# SCH_System.net
KiCad netlist of a schematic drawn in Altium Designer
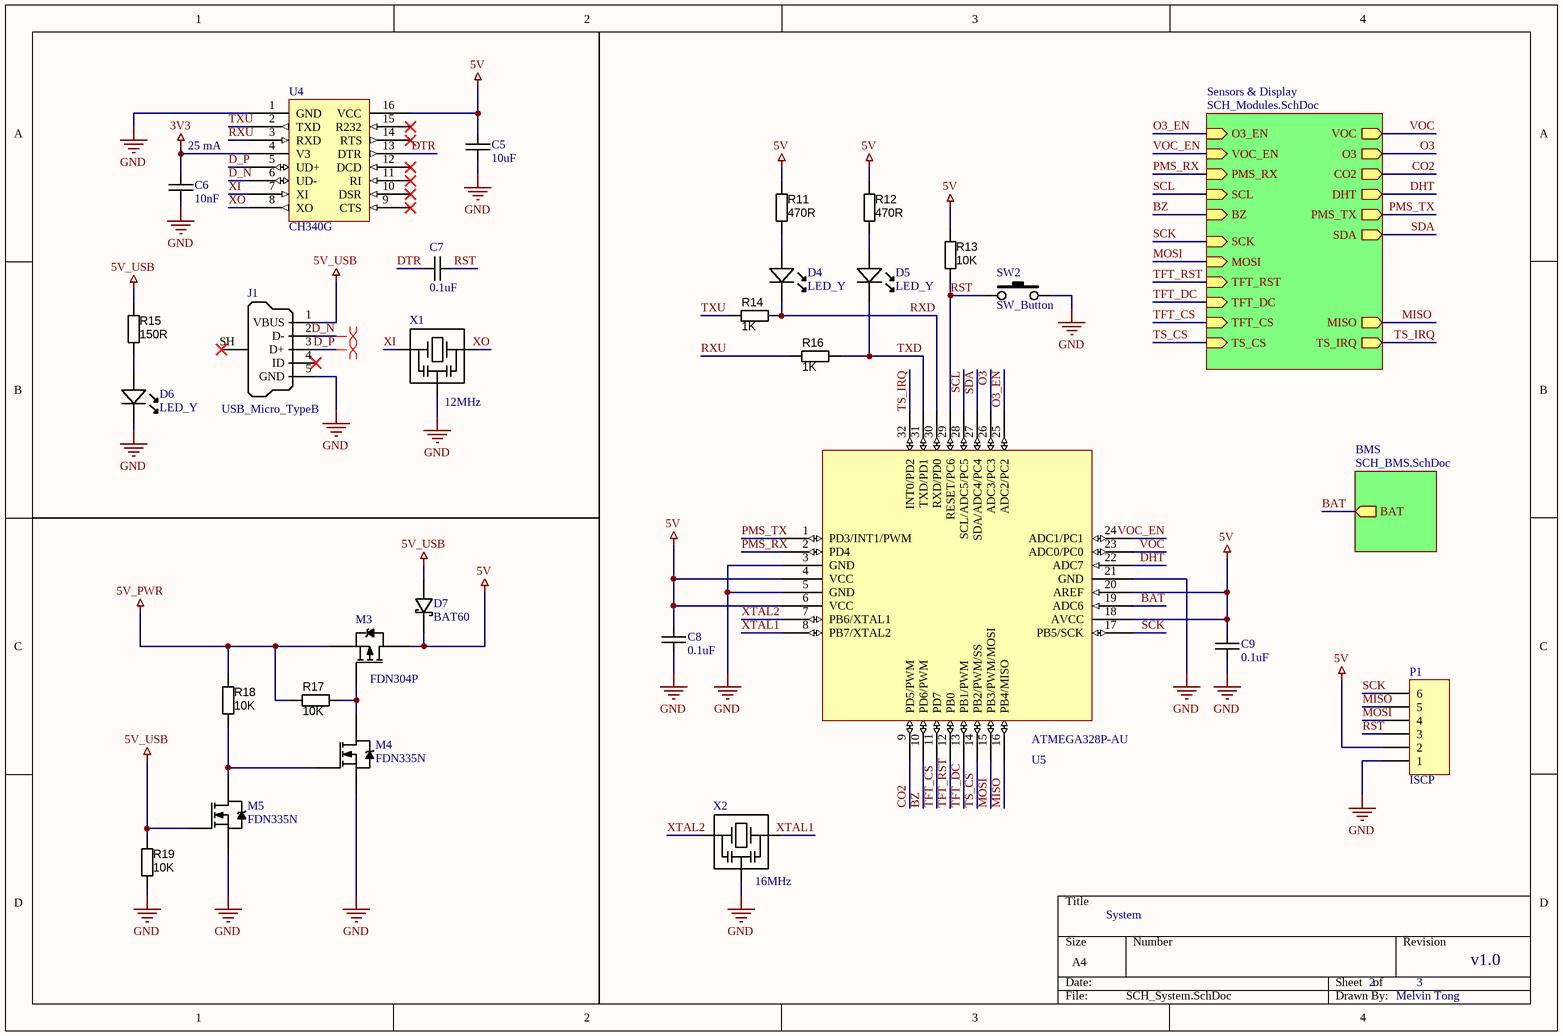
[diagram p0: SCH_System.SchDoc]

(export (version "E")
  (design (tool "Eeschema 10.0.6"))
  (components
    (comp (ref "C5")
      (value "10uF")
      (footprint "CAP_0805")
      (description "SMD 0805")
      (libsource (lib "SchLib_AirMeter") (part "CAP_10uF"))
    )
    (comp (ref "C6")
      (value "10nF")
      (footprint "CAP_0805")
      (description "SMD 0805")
      (libsource (lib "SchLib_AirMeter") (part "CAP_10nF"))
    )
    (comp (ref "C7")
      (value "0.1uF")
      (footprint "CAP_0805")
      (description "SMD 0805")
      (libsource (lib "SchLib_AirMeter") (part "CAP_0.1uF"))
    )
    (comp (ref "C8")
      (value "0.1uF")
      (footprint "CAP_0805")
      (description "SMD 0805")
      (libsource (lib "SchLib_AirMeter") (part "CAP_0.1uF"))
    )
    (comp (ref "C9")
      (value "0.1uF")
      (footprint "CAP_0805")
      (description "SMD 0805")
      (libsource (lib "SchLib_AirMeter") (part "CAP_0.1uF"))
    )
    (comp (ref "D4")
      (value "LED_Y")
      (footprint "LED_0805")
      (description "SMD_0805 2.4V")
      (libsource (lib "SchLib_AirMeter") (part "LED_Y"))
    )
    (comp (ref "D5")
      (value "LED_Y")
      (footprint "LED_0805")
      (description "SMD_0805 2.4V")
      (libsource (lib "SchLib_AirMeter") (part "LED_Y"))
    )
    (comp (ref "D6")
      (value "LED_Y")
      (footprint "LED_0805")
      (description "SMD_0805 2.4V")
      (libsource (lib "SchLib_AirMeter") (part "LED_Y"))
    )
    (comp (ref "D7")
      (value "BAT60")
      (footprint "SOD323")
      (description "Schottky Diode 3A, Vf~0.24V, Vr=10V")
      (libsource (lib "SchLib_AirMeter") (part "BAT60"))
    )
    (comp (ref "J1")
      (value "USB_Micro_TypeB")
      (footprint "USB_Micro_TypeB")
      (libsource (lib "SchLib_AirMeter") (part "USB_Micro_TypeB"))
    )
    (comp (ref "M3")
      (value "FDN304P")
      (footprint "SOT23_213")
      (libsource (lib "SchLib_AirMeter") (part "PMOS"))
    )
    (comp (ref "M4")
      (value "FDN335N")
      (footprint "SOT23_213")
      (libsource (lib "SchLib_AirMeter") (part "NMOS"))
    )
    (comp (ref "M5")
      (value "FDN335N")
      (footprint "SOT23_213")
      (libsource (lib "SchLib_AirMeter") (part "NMOS"))
    )
    (comp (ref "P1")
      (value "ISCP")
      (footprint "HDR1X6")
      (description "Header, 6-Pin")
      (fields (field (name "PUBLISHER") "Altium Limited"))
      (libsource (lib "Miscellaneous Connectors") (part "Header 6"))
    )
    (comp (ref "R11")
      (value "470R")
      (footprint "RESC3216X70N")
      (description "Resistor SMD, 1206")
      (libsource (lib "Schlib_Sword") (part "RES_470R"))
    )
    (comp (ref "R12")
      (value "470R")
      (footprint "RESC3216X70N")
      (description "Resistor SMD, 1206")
      (libsource (lib "") (part "RES_470R_1"))
    )
    (comp (ref "R13")
      (value "10K")
      (footprint "RESC3216X70N")
      (description "Resistor SMD, 1206")
      (libsource (lib "SchLib_AirMeter") (part "RES_10K"))
    )
    (comp (ref "R14")
      (value "1K")
      (footprint "RESC3216X70N")
      (description "Resistor SMD, 1206")
      (libsource (lib "SchLib_AirMeter") (part "RES_1K"))
    )
    (comp (ref "R15")
      (value "150R")
      (footprint "RESC3216X70N")
      (description "Resistor SMD, 1206")
      (libsource (lib "SchLib_AirMeter") (part "RES_150R"))
    )
    (comp (ref "R16")
      (value "1K")
      (footprint "RESC3216X70N")
      (description "Resistor SMD, 1206")
      (libsource (lib "SchLib_AirMeter") (part "RES_1K"))
    )
    (comp (ref "R17")
      (value "10K")
      (footprint "RESC3216X70N")
      (description "Resistor SMD, 1206")
      (libsource (lib "") (part "RES_10K_1"))
    )
    (comp (ref "R18")
      (value "10K")
      (footprint "RESC3216X70N")
      (description "Resistor SMD, 1206")
      (libsource (lib "SchLib_AirMeter") (part "RES_10K"))
    )
    (comp (ref "R19")
      (value "10K")
      (footprint "RESC3216X70N")
      (description "Resistor SMD, 1206")
      (libsource (lib "SchLib_AirMeter") (part "RES_10K"))
    )
    (comp (ref "SW2")
      (value "SW_Button")
      (footprint "Button_4x4x1.5")
      (libsource (lib "SchLib_AirMeter") (part "SW_Button"))
    )
    (comp (ref "U4")
      (value "CH340G")
      (footprint "CH340G")
      (libsource (lib "SchLib_AirMeter") (part "CH340G"))
    )
    (comp (ref "U5")
      (value "ATMEGA328P-AU")
      (footprint "ATMEGA328P-AU")
      (libsource (lib "SchLib_AirMeter") (part "ATMEGA328P-AU"))
    )
    (comp (ref "X1")
      (value "12MHz")
      (footprint "XTAL_3.2x1.6")
      (description "Crystal Oscillator")
      (libsource (lib "SchLib_AirMeter") (part "12MHz"))
    )
    (comp (ref "X2")
      (value "16MHz")
      (footprint "XTAL_3.2x1.6")
      (description "Crystal Oscillator")
      (libsource (lib "SchLib_AirMeter") (part "16MHz"))
    )
  )
  (nets
    (net (code "1") (name "/BAT") (class "Default")
      (node (ref "U5") (pin "19") (pinfunction "ADC6_19") (pintype "input"))
    )
    (net (code "2") (name "/BZ") (class "Default")
      (node (ref "U5") (pin "10") (pinfunction "PD6/PWM_10") (pintype "bidirectional"))
    )
    (net (code "3") (name "/CO2") (class "Default")
      (node (ref "U5") (pin "9") (pinfunction "PD5/PWM_9") (pintype "bidirectional"))
    )
    (net (code "4") (name "/DHT") (class "Default")
      (node (ref "U5") (pin "22") (pinfunction "ADC7_22") (pintype "input"))
    )
    (net (code "5") (name "/DTR") (class "Default")
      (node (ref "C7") (pin "1") (pintype "passive"))
      (node (ref "U4") (pin "13") (pinfunction "DTR_13") (pintype "output"))
    )
    (net (code "6") (name "/D_N") (class "Default")
      (node (ref "J1") (pin "2") (pinfunction "D-_2") (pintype "passive"))
      (node (ref "U4") (pin "6") (pinfunction "UD-_6") (pintype "bidirectional"))
    )
    (net (code "7") (name "/D_P") (class "Default")
      (node (ref "J1") (pin "3") (pinfunction "D+_3") (pintype "passive"))
      (node (ref "U4") (pin "5") (pinfunction "UD+_5") (pintype "bidirectional"))
    )
    (net (code "8") (name "/MISO") (class "Default")
      (node (ref "P1") (pin "5") (pinfunction "5_5") (pintype "passive"))
      (node (ref "U5") (pin "16") (pinfunction "PB4/MISO_16") (pintype "bidirectional"))
    )
    (net (code "9") (name "/MOSI") (class "Default")
      (node (ref "P1") (pin "4") (pinfunction "4_4") (pintype "passive"))
      (node (ref "U5") (pin "15") (pinfunction "PB3/PWM/MOSI_15") (pintype "bidirectional"))
    )
    (net (code "10") (name "/O3") (class "Default")
      (node (ref "U5") (pin "26") (pinfunction "ADC3/PC3_26") (pintype "bidirectional"))
    )
    (net (code "11") (name "/O3_EN") (class "Default")
      (node (ref "U5") (pin "25") (pinfunction "ADC2/PC2_25") (pintype "bidirectional"))
    )
    (net (code "12") (name "/PMS_RX") (class "Default")
      (node (ref "U5") (pin "2") (pinfunction "PD4_2") (pintype "bidirectional"))
    )
    (net (code "13") (name "/PMS_TX") (class "Default")
      (node (ref "U5") (pin "1") (pinfunction "PD3/INT1/PWM_1") (pintype "bidirectional"))
    )
    (net (code "14") (name "/RST") (class "Default")
      (node (ref "C7") (pin "2") (pintype "passive"))
      (node (ref "P1") (pin "3") (pinfunction "3_3") (pintype "passive"))
      (node (ref "R13") (pin "2") (pinfunction "2_2") (pintype "passive"))
      (node (ref "SW2") (pin "1") (pintype "passive"))
      (node (ref "U5") (pin "29") (pinfunction "RESET/PC6_29") (pintype "bidirectional"))
    )
    (net (code "15") (name "/RXD") (class "Default")
      (node (ref "D4") (pin "K") (pinfunction "K_K") (pintype "passive"))
      (node (ref "R14") (pin "2") (pinfunction "2_2") (pintype "passive"))
      (node (ref "U5") (pin "30") (pinfunction "RXD/PD0_30") (pintype "bidirectional"))
    )
    (net (code "16") (name "/RXU") (class "Default")
      (node (ref "R16") (pin "1") (pinfunction "1_1") (pintype "passive"))
      (node (ref "U4") (pin "3") (pinfunction "RXD_3") (pintype "input"))
    )
    (net (code "17") (name "/SCK") (class "Default")
      (node (ref "P1") (pin "6") (pinfunction "6_6") (pintype "passive"))
      (node (ref "U5") (pin "17") (pinfunction "PB5/SCK_17") (pintype "bidirectional"))
    )
    (net (code "18") (name "/SCL") (class "Default")
      (node (ref "U5") (pin "28") (pinfunction "SCL/ADC5/PC5_28") (pintype "bidirectional"))
    )
    (net (code "19") (name "/SDA") (class "Default")
      (node (ref "U5") (pin "27") (pinfunction "SDA/ADC4/PC4_27") (pintype "bidirectional"))
    )
    (net (code "20") (name "/TFT_CS") (class "Default")
      (node (ref "U5") (pin "11") (pinfunction "PD7_11") (pintype "bidirectional"))
    )
    (net (code "21") (name "/TFT_DC") (class "Default")
      (node (ref "U5") (pin "13") (pinfunction "PB1/PWM_13") (pintype "bidirectional"))
    )
    (net (code "22") (name "/TFT_RST") (class "Default")
      (node (ref "U5") (pin "12") (pinfunction "PB0_12") (pintype "bidirectional"))
    )
    (net (code "23") (name "/TS_CS") (class "Default")
      (node (ref "U5") (pin "14") (pinfunction "PB2/PWM/SS_14") (pintype "bidirectional"))
    )
    (net (code "24") (name "/TS_IRQ") (class "Default")
      (node (ref "U5") (pin "32") (pinfunction "INT0/PD2_32") (pintype "bidirectional"))
    )
    (net (code "25") (name "/TXD") (class "Default")
      (node (ref "D5") (pin "K") (pinfunction "K_K") (pintype "passive"))
      (node (ref "R16") (pin "2") (pinfunction "2_2") (pintype "passive"))
      (node (ref "U5") (pin "31") (pinfunction "TXD/PD1_31") (pintype "bidirectional"))
    )
    (net (code "26") (name "/TXU") (class "Default")
      (node (ref "R14") (pin "1") (pinfunction "1_1") (pintype "passive"))
      (node (ref "U4") (pin "2") (pinfunction "TXD_2") (pintype "output"))
    )
    (net (code "27") (name "/VOC") (class "Default")
      (node (ref "U5") (pin "23") (pinfunction "ADC0/PC0_23") (pintype "bidirectional"))
    )
    (net (code "28") (name "/VOC_EN") (class "Default")
      (node (ref "U5") (pin "24") (pinfunction "ADC1/PC1_24") (pintype "bidirectional"))
    )
    (net (code "29") (name "/XI") (class "Default")
      (node (ref "U4") (pin "7") (pinfunction "XI_7") (pintype "input"))
      (node (ref "X1") (pin "1") (pinfunction "IN_1") (pintype "passive"))
    )
    (net (code "30") (name "/XO") (class "Default")
      (node (ref "U4") (pin "8") (pinfunction "XO_8") (pintype "output"))
      (node (ref "X1") (pin "3") (pinfunction "OUT_3") (pintype "passive"))
    )
    (net (code "31") (name "/XTAL1") (class "Default")
      (node (ref "U5") (pin "8") (pinfunction "PB7/XTAL2_8") (pintype "bidirectional"))
      (node (ref "X2") (pin "3") (pinfunction "OUT_3") (pintype "passive"))
    )
    (net (code "32") (name "/XTAL2") (class "Default")
      (node (ref "U5") (pin "7") (pinfunction "PB6/XTAL1_7") (pintype "bidirectional"))
      (node (ref "X2") (pin "1") (pinfunction "IN_1") (pintype "passive"))
    )
    (net (code "33") (name "3V3") (class "Default")
      (node (ref "C6") (pin "1") (pintype "passive"))
      (node (ref "U4") (pin "4") (pinfunction "V3_4") (pintype "power_in"))
    )
    (net (code "34") (name "5V") (class "Default")
      (node (ref "C5") (pin "1") (pintype "passive"))
      (node (ref "C8") (pin "1") (pintype "passive"))
      (node (ref "C9") (pin "1") (pintype "passive"))
      (node (ref "D7") (pin "K") (pinfunction "K_K") (pintype "passive"))
      (node (ref "M3") (pin "3") (pinfunction "D_3") (pintype "passive"))
      (node (ref "P1") (pin "2") (pinfunction "2_2") (pintype "passive"))
      (node (ref "R11") (pin "2") (pinfunction "2_2") (pintype "passive"))
      (node (ref "R12") (pin "1") (pinfunction "1_1") (pintype "passive"))
      (node (ref "R13") (pin "1") (pinfunction "1_1") (pintype "passive"))
      (node (ref "U4") (pin "16") (pinfunction "VCC_16") (pintype "power_in"))
      (node (ref "U5") (pin "18") (pinfunction "AVCC_18") (pintype "power_in"))
      (node (ref "U5") (pin "20") (pinfunction "AREF_20") (pintype "input"))
      (node (ref "U5") (pin "4") (pinfunction "VCC_4") (pintype "power_in"))
      (node (ref "U5") (pin "6") (pinfunction "VCC_6") (pintype "power_in"))
    )
    (net (code "35") (name "5V_PWR") (class "Default")
      (node (ref "M3") (pin "2") (pinfunction "S_2") (pintype "passive"))
      (node (ref "R17") (pin "1") (pinfunction "1_1") (pintype "passive"))
      (node (ref "R18") (pin "1") (pinfunction "1_1") (pintype "passive"))
    )
    (net (code "36") (name "5V_USB") (class "Default")
      (node (ref "D7") (pin "A") (pinfunction "A_A") (pintype "passive"))
      (node (ref "J1") (pin "1") (pinfunction "VBUS_1") (pintype "passive"))
      (node (ref "M5") (pin "1") (pinfunction "G_1") (pintype "passive"))
      (node (ref "R15") (pin "1") (pinfunction "1_1") (pintype "passive"))
      (node (ref "R19") (pin "1") (pinfunction "1_1") (pintype "passive"))
    )
    (net (code "37") (name "GND") (class "Default")
      (node (ref "C5") (pin "2") (pintype "passive"))
      (node (ref "C6") (pin "2") (pintype "passive"))
      (node (ref "C8") (pin "2") (pintype "passive"))
      (node (ref "C9") (pin "2") (pintype "passive"))
      (node (ref "D6") (pin "K") (pinfunction "K_K") (pintype "passive"))
      (node (ref "J1") (pin "5") (pinfunction "GND_5") (pintype "passive"))
      (node (ref "M4") (pin "2") (pinfunction "S_2") (pintype "passive"))
      (node (ref "M5") (pin "2") (pinfunction "S_2") (pintype "passive"))
      (node (ref "P1") (pin "1") (pinfunction "1_1") (pintype "passive"))
      (node (ref "R19") (pin "2") (pinfunction "2_2") (pintype "passive"))
      (node (ref "SW2") (pin "2") (pintype "passive"))
      (node (ref "U4") (pin "1") (pinfunction "GND_1") (pintype "power_in"))
      (node (ref "U5") (pin "21") (pinfunction "GND_21") (pintype "power_in"))
      (node (ref "U5") (pin "3") (pinfunction "GND_3") (pintype "power_in"))
      (node (ref "U5") (pin "5") (pinfunction "GND_5") (pintype "power_in"))
      (node (ref "X1") (pin "2") (pinfunction "GND_2") (pintype "passive"))
      (node (ref "X2") (pin "2") (pinfunction "GND_2") (pintype "passive"))
    )
    (net (code "38") (name "Net-(D4-PadA)") (class "Default")
      (node (ref "D4") (pin "A") (pinfunction "A_A") (pintype "passive"))
      (node (ref "R11") (pin "1") (pinfunction "1_1") (pintype "passive"))
    )
    (net (code "39") (name "Net-(D5-PadA)") (class "Default")
      (node (ref "D5") (pin "A") (pinfunction "A_A") (pintype "passive"))
      (node (ref "R12") (pin "2") (pinfunction "2_2") (pintype "passive"))
    )
    (net (code "40") (name "Net-(D6-PadA)") (class "Default")
      (node (ref "D6") (pin "A") (pinfunction "A_A") (pintype "passive"))
      (node (ref "R15") (pin "2") (pinfunction "2_2") (pintype "passive"))
    )
    (net (code "41") (name "Net-(M3-G)") (class "Default")
      (node (ref "M3") (pin "1") (pinfunction "G_1") (pintype "passive"))
      (node (ref "M4") (pin "3") (pinfunction "D_3") (pintype "passive"))
      (node (ref "R17") (pin "2") (pinfunction "2_2") (pintype "passive"))
    )
    (net (code "42") (name "Net-(M4-G)") (class "Default")
      (node (ref "M4") (pin "1") (pinfunction "G_1") (pintype "passive"))
      (node (ref "M5") (pin "3") (pinfunction "D_3") (pintype "passive"))
      (node (ref "R18") (pin "2") (pinfunction "2_2") (pintype "passive"))
    )
    (net (code "43") (name "unconnected-(J1-ID-Pad4)") (class "Default")
      (node (ref "J1") (pin "4") (pinfunction "ID_4") (pintype "passive+no_connect"))
    )
    (net (code "44") (name "unconnected-(J1-Shell-PadSH)") (class "Default")
      (node (ref "J1") (pin "SH") (pinfunction "Shell_SH") (pintype "passive+no_connect"))
    )
    (net (code "45") (name "unconnected-(U4-CTS-Pad9)") (class "Default")
      (node (ref "U4") (pin "9") (pinfunction "CTS_9") (pintype "input+no_connect"))
    )
    (net (code "46") (name "unconnected-(U4-DCD-Pad12)") (class "Default")
      (node (ref "U4") (pin "12") (pinfunction "DCD_12") (pintype "input+no_connect"))
    )
    (net (code "47") (name "unconnected-(U4-DSR-Pad10)") (class "Default")
      (node (ref "U4") (pin "10") (pinfunction "DSR_10") (pintype "input+no_connect"))
    )
    (net (code "48") (name "unconnected-(U4-R232-Pad15)") (class "Default")
      (node (ref "U4") (pin "15") (pinfunction "R232_15") (pintype "input+no_connect"))
    )
    (net (code "49") (name "unconnected-(U4-RI-Pad11)") (class "Default")
      (node (ref "U4") (pin "11") (pinfunction "RI_11") (pintype "input+no_connect"))
    )
    (net (code "50") (name "unconnected-(U4-RTS-Pad14)") (class "Default")
      (node (ref "U4") (pin "14") (pinfunction "RTS_14") (pintype "output+no_connect"))
    )
  )
)
